# design.net
KiCad netlist of a schematic drawn in Altium Designer
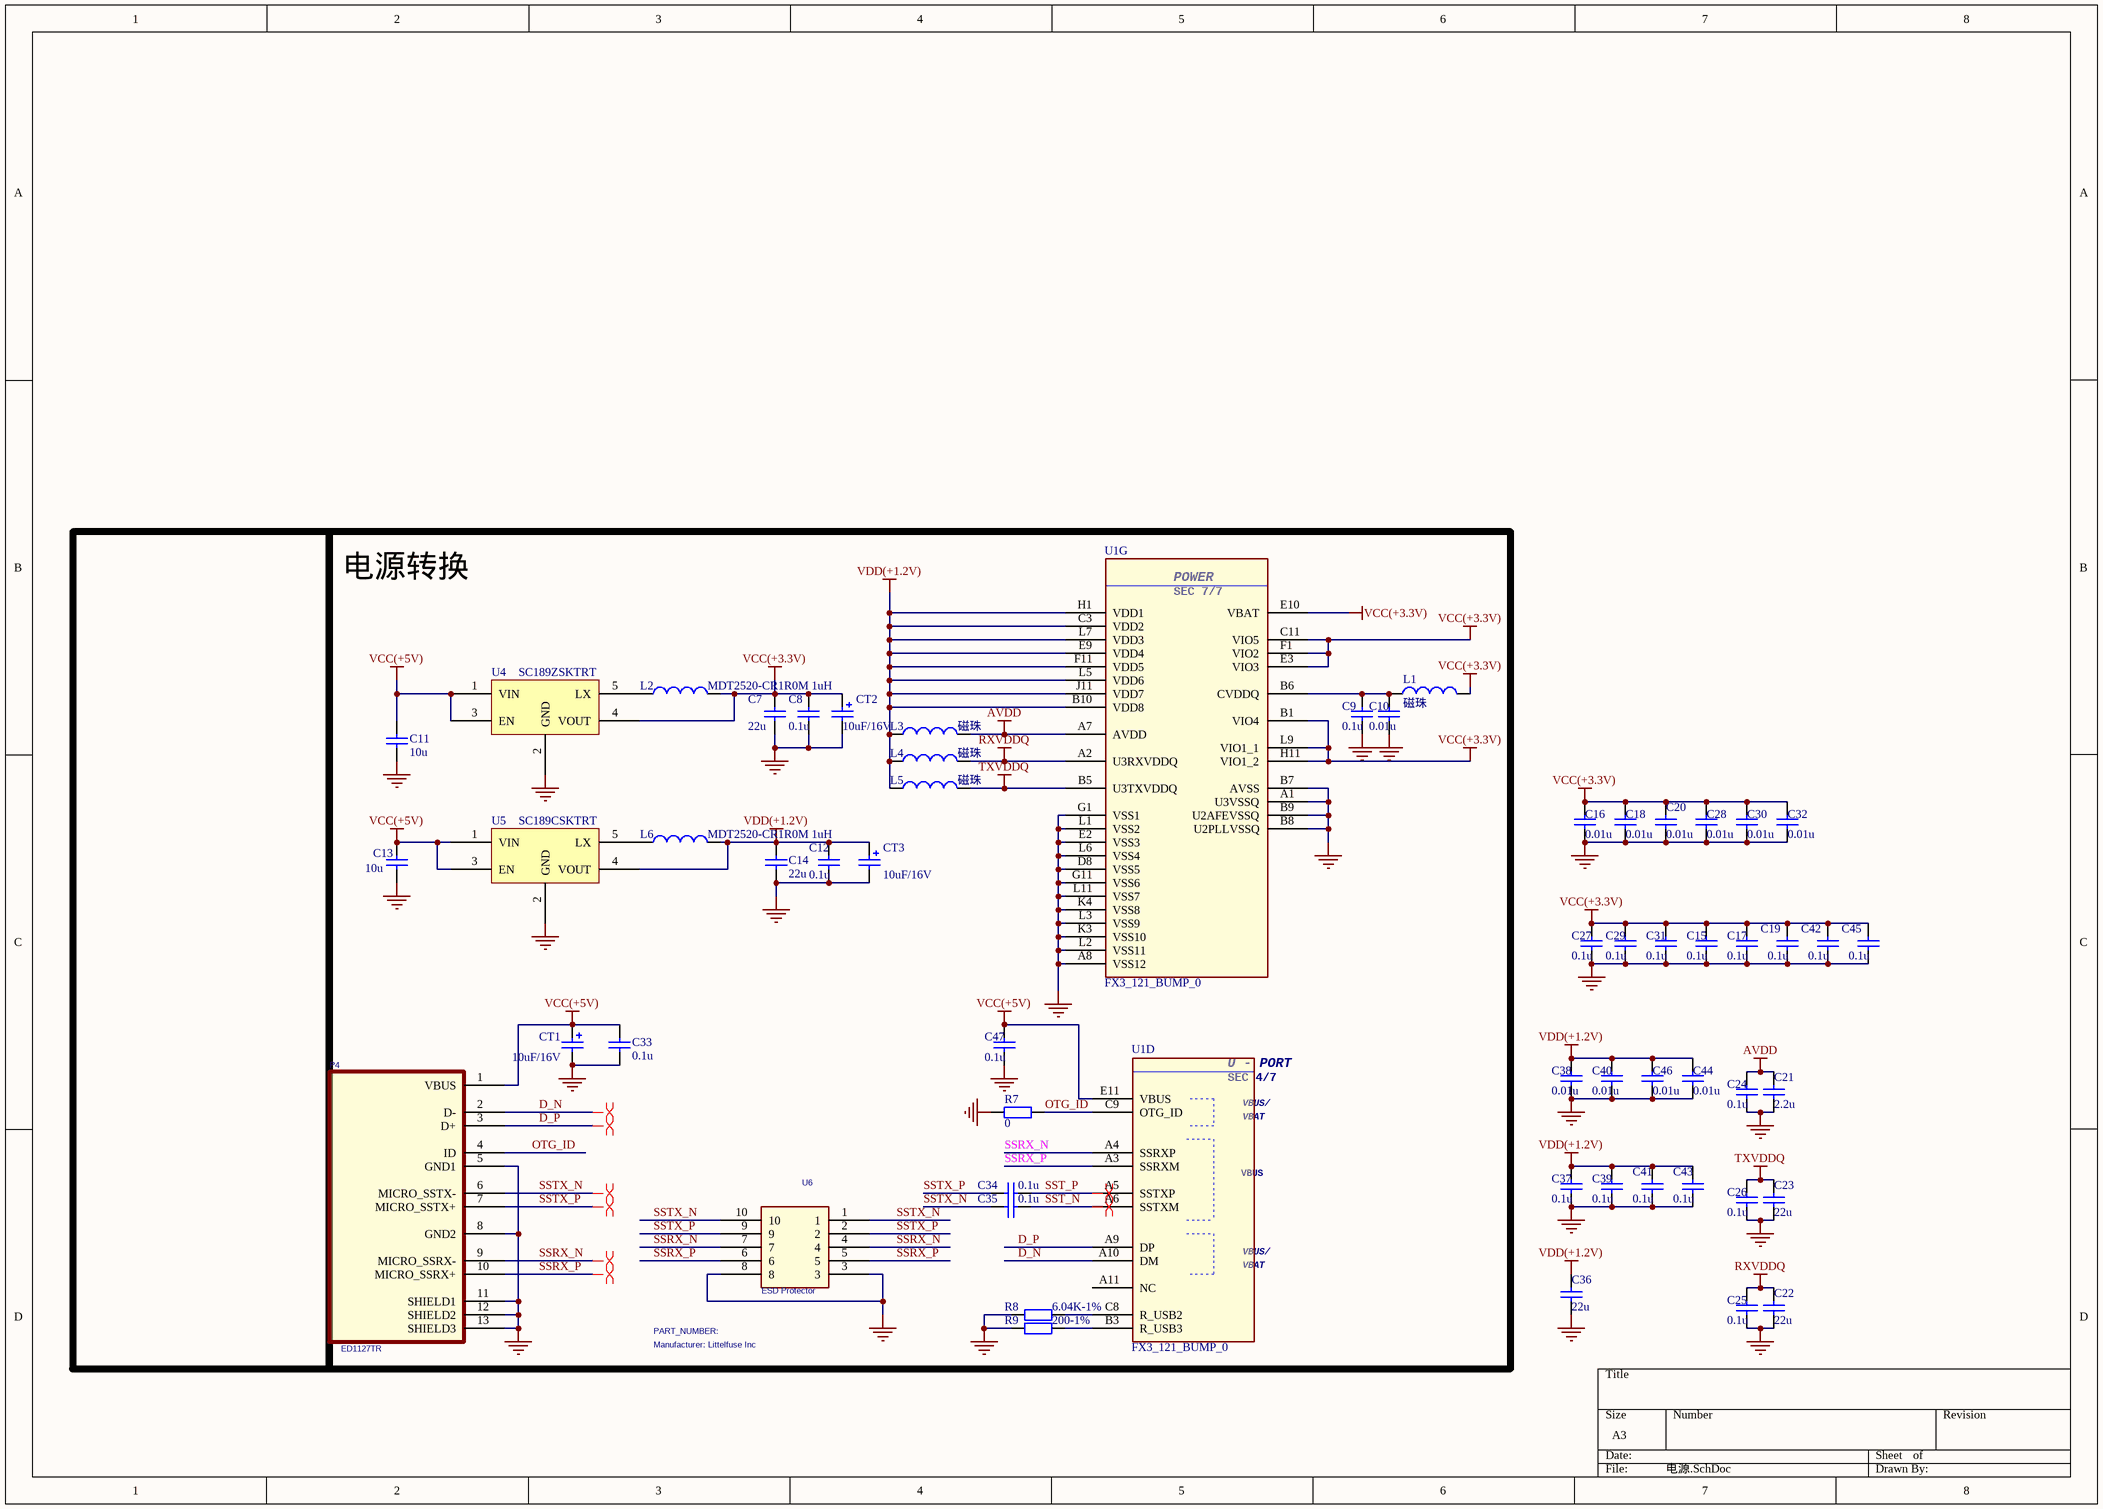
[diagram p0: 电源.SchDoc]

(export (version "E")
  (design (tool "Eeschema 10.0.6"))
  (components
    (comp (ref "C7")
      (value "22u")
      (footprint "C0805S-CAP")
      (description "Capacitor")
      (fields (field (name "PUBLISHER") "Altium Limited"))
      (libsource (lib "USB_CAMERA") (part "CAP0805"))
    )
    (comp (ref "C8")
      (value "0.1u")
      (footprint "0603S-CAP")
      (description "Capacitor")
      (fields (field (name "PUBLISHER") "Altium Limited"))
      (libsource (lib "USB_CAMERA") (part "CAP0805"))
    )
    (comp (ref "C9")
      (value "0.1u")
      (footprint "C0402")
      (description "Capacitor")
      (fields (field (name "PUBLISHER") "Altium Limited"))
      (libsource (lib "WM360") (part "CAP0805"))
    )
    (comp (ref "C10")
      (value "0.01u")
      (footprint "C0402")
      (description "Capacitor")
      (fields (field (name "PUBLISHER") "Altium Limited"))
      (libsource (lib "WM360") (part "CAP0805"))
    )
    (comp (ref "C11")
      (value "10u")
      (footprint "C0805S-CAP")
      (description "Capacitor")
      (fields (field (name "PUBLISHER") "Altium Limited"))
      (libsource (lib "USB_CAMERA") (part "CAP0805"))
    )
    (comp (ref "C12")
      (value "0.1u")
      (footprint "0603S-CAP")
      (description "Capacitor")
      (fields (field (name "PUBLISHER") "Altium Limited"))
      (libsource (lib "USB_CAMERA") (part "CAP0805"))
    )
    (comp (ref "C13")
      (value "10u")
      (footprint "C0805S-CAP")
      (description "Capacitor")
      (fields (field (name "PUBLISHER") "Altium Limited"))
      (libsource (lib "Miscellaneous Devices") (part "Cap"))
    )
    (comp (ref "C14")
      (value "22u")
      (footprint "C0805S-CAP")
      (description "Capacitor")
      (fields (field (name "PUBLISHER") "Altium Limited"))
      (libsource (lib "USB_CAMERA") (part "CAP0805"))
    )
    (comp (ref "C15")
      (value "0.1u")
      (footprint "C0402")
      (description "Capacitor")
      (fields (field (name "PUBLISHER") "Altium Limited"))
      (libsource (lib "WM360") (part "CAP0805"))
    )
    (comp (ref "C16")
      (value "0.01u")
      (footprint "C0402")
      (description "Capacitor")
      (fields (field (name "PUBLISHER") "Altium Limited"))
      (libsource (lib "WM360") (part "CAP0805"))
    )
    (comp (ref "C17")
      (value "0.1u")
      (footprint "C0402")
      (description "Capacitor")
      (fields (field (name "PUBLISHER") "Altium Limited"))
      (libsource (lib "WM360") (part "CAP0805"))
    )
    (comp (ref "C18")
      (value "0.01u")
      (footprint "C0402")
      (description "Capacitor")
      (fields (field (name "PUBLISHER") "Altium Limited"))
      (libsource (lib "WM360") (part "CAP0805"))
    )
    (comp (ref "C19")
      (value "0.1u")
      (footprint "C0402")
      (description "Capacitor")
      (fields (field (name "PUBLISHER") "Altium Limited"))
      (libsource (lib "WM360") (part "CAP0805"))
    )
    (comp (ref "C20")
      (value "0.01u")
      (footprint "C0402")
      (description "Capacitor")
      (fields (field (name "PUBLISHER") "Altium Limited"))
      (libsource (lib "WM360") (part "CAP0805"))
    )
    (comp (ref "C21")
      (value "2.2u")
      (footprint "C0805S-CAP")
      (description "Capacitor")
      (fields (field (name "PUBLISHER") "Altium Limited"))
      (libsource (lib "USB_CAMERA") (part "CAP0805"))
    )
    (comp (ref "C22")
      (value "22u")
      (footprint "C0805S-CAP")
      (description "Capacitor")
      (fields (field (name "PUBLISHER") "Altium Limited"))
      (libsource (lib "USB_CAMERA") (part "CAP0805"))
    )
    (comp (ref "C23")
      (value "22u")
      (footprint "C0805S-CAP")
      (description "Capacitor")
      (fields (field (name "PUBLISHER") "Altium Limited"))
      (libsource (lib "USB_CAMERA") (part "CAP0805"))
    )
    (comp (ref "C24")
      (value "0.1u")
      (footprint "C0402")
      (description "Capacitor")
      (fields (field (name "PUBLISHER") "Altium Limited"))
      (libsource (lib "WM360") (part "CAP0805"))
    )
    (comp (ref "C25")
      (value "0.1u")
      (footprint "C0402")
      (description "Capacitor")
      (fields (field (name "PUBLISHER") "Altium Limited"))
      (libsource (lib "WM360") (part "CAP0805"))
    )
    (comp (ref "C26")
      (value "0.1u")
      (footprint "C0402")
      (description "Capacitor")
      (fields (field (name "PUBLISHER") "Altium Limited"))
      (libsource (lib "WM360") (part "CAP0805"))
    )
    (comp (ref "C27")
      (value "0.1u")
      (footprint "C0402")
      (description "Capacitor")
      (fields (field (name "PUBLISHER") "Altium Limited"))
      (libsource (lib "WM360") (part "CAP0805"))
    )
    (comp (ref "C28")
      (value "0.01u")
      (footprint "C0402")
      (description "Capacitor")
      (fields (field (name "PUBLISHER") "Altium Limited"))
      (libsource (lib "WM360") (part "CAP0805"))
    )
    (comp (ref "C29")
      (value "0.1u")
      (footprint "C0402")
      (description "Capacitor")
      (fields (field (name "PUBLISHER") "Altium Limited"))
      (libsource (lib "WM360") (part "CAP0805"))
    )
    (comp (ref "C30")
      (value "0.01u")
      (footprint "C0402")
      (description "Capacitor")
      (fields (field (name "PUBLISHER") "Altium Limited"))
      (libsource (lib "WM360") (part "CAP0805"))
    )
    (comp (ref "C31")
      (value "0.1u")
      (footprint "C0402")
      (description "Capacitor")
      (fields (field (name "PUBLISHER") "Altium Limited"))
      (libsource (lib "WM360") (part "CAP0805"))
    )
    (comp (ref "C32")
      (value "0.01u")
      (footprint "C0402")
      (description "Capacitor")
      (fields (field (name "PUBLISHER") "Altium Limited"))
      (libsource (lib "WM360") (part "CAP0805"))
    )
    (comp (ref "C33")
      (value "0.1u")
      (footprint "0603S-CAP")
      (description "Capacitor")
      (fields (field (name "PUBLISHER") "Altium Limited"))
      (libsource (lib "USB_CAMERA") (part "CAP0805"))
    )
    (comp (ref "C34")
      (value "0.1u")
      (footprint "C0402")
      (description "Capacitor")
      (fields (field (name "PUBLISHER") "Altium Limited"))
      (libsource (lib "WM360") (part "CAP0805"))
    )
    (comp (ref "C35")
      (value "0.1u")
      (footprint "C0402")
      (description "Capacitor")
      (fields (field (name "PUBLISHER") "Altium Limited"))
      (libsource (lib "WM360") (part "CAP0805"))
    )
    (comp (ref "C36")
      (value "22u")
      (footprint "C0805S-CAP")
      (description "Capacitor")
      (fields (field (name "PUBLISHER") "Altium Limited"))
      (libsource (lib "USB_CAMERA") (part "CAP0805"))
    )
    (comp (ref "C37")
      (value "0.1u")
      (footprint "C0402")
      (description "Capacitor")
      (fields (field (name "PUBLISHER") "Altium Limited"))
      (libsource (lib "WM360") (part "CAP0805"))
    )
    (comp (ref "C38")
      (value "0.01u")
      (footprint "C0402")
      (description "Capacitor")
      (fields (field (name "PUBLISHER") "Altium Limited"))
      (libsource (lib "WM360") (part "CAP0805"))
    )
    (comp (ref "C39")
      (value "0.1u")
      (footprint "C0402")
      (description "Capacitor")
      (fields (field (name "PUBLISHER") "Altium Limited"))
      (libsource (lib "WM360") (part "CAP0805"))
    )
    (comp (ref "C40")
      (value "0.01u")
      (footprint "C0402")
      (description "Capacitor")
      (fields (field (name "PUBLISHER") "Altium Limited"))
      (libsource (lib "WM360") (part "CAP0805"))
    )
    (comp (ref "C41")
      (value "0.1u")
      (footprint "C0402")
      (description "Capacitor")
      (fields (field (name "PUBLISHER") "Altium Limited"))
      (libsource (lib "WM360") (part "CAP0805"))
    )
    (comp (ref "C42")
      (value "0.1u")
      (footprint "C0402")
      (description "Capacitor")
      (fields (field (name "PUBLISHER") "Altium Limited"))
      (libsource (lib "WM360") (part "CAP0805"))
    )
    (comp (ref "C43")
      (value "0.1u")
      (footprint "C0402")
      (description "Capacitor")
      (fields (field (name "PUBLISHER") "Altium Limited"))
      (libsource (lib "WM360") (part "CAP0805"))
    )
    (comp (ref "C44")
      (value "0.01u")
      (footprint "C0402")
      (description "Capacitor")
      (fields (field (name "PUBLISHER") "Altium Limited"))
      (libsource (lib "WM360") (part "CAP0805"))
    )
    (comp (ref "C45")
      (value "0.1u")
      (footprint "C0402")
      (description "Capacitor")
      (fields (field (name "PUBLISHER") "Altium Limited"))
      (libsource (lib "WM360") (part "CAP0805"))
    )
    (comp (ref "C46")
      (value "0.01u")
      (footprint "C0402")
      (description "Capacitor")
      (fields (field (name "PUBLISHER") "Altium Limited"))
      (libsource (lib "WM360") (part "CAP0805"))
    )
    (comp (ref "C47")
      (value "0.1u")
      (footprint "C0402")
      (description "Capacitor")
      (fields (field (name "PUBLISHER") "Altium Limited"))
      (libsource (lib "WM360") (part "CAP0805"))
    )
    (comp (ref "CT1")
      (value "10uF/16V")
      (footprint "钽电容（A型）")
      (description "Polarized Capacitor (Axial)")
      (fields (field (name "PUBLISHER") "Altium Limited"))
      (libsource (lib "Miscellaneous Devices") (part "Cap Pol2"))
    )
    (comp (ref "CT2")
      (value "10uF/16V")
      (footprint "钽电容（A型）")
      (description "Polarized Capacitor (Axial)")
      (fields (field (name "PUBLISHER") "Altium Limited"))
      (libsource (lib "Miscellaneous Devices") (part "Cap Pol2"))
    )
    (comp (ref "CT3")
      (value "10uF/16V")
      (footprint "钽电容（A型）")
      (description "Polarized Capacitor (Axial)")
      (fields (field (name "PUBLISHER") "Altium Limited"))
      (libsource (lib "Miscellaneous Devices") (part "Cap Pol2"))
    )
    (comp (ref "L1")
      (value "磁珠")
      (footprint "L0603")
      (description "Inductor")
      (fields (field (name "PUBLISHER") "Altium Limited"))
      (libsource (lib "Miscellaneous Devices") (part "Inductor"))
    )
    (comp (ref "L2")
      (value "MDT2520-CR1R0M 1uH")
      (footprint "L2520")
      (description "Inductor")
      (fields (field (name "PUBLISHER") "Altium Limited"))
      (libsource (lib "Miscellaneous Devices") (part "Inductor"))
    )
    (comp (ref "L3")
      (value "磁珠")
      (footprint "L0603")
      (description "Inductor")
      (fields (field (name "PUBLISHER") "Altium Limited"))
      (libsource (lib "Miscellaneous Devices") (part "Inductor"))
    )
    (comp (ref "L4")
      (value "磁珠")
      (footprint "L0603")
      (description "Inductor")
      (fields (field (name "PUBLISHER") "Altium Limited"))
      (libsource (lib "Miscellaneous Devices") (part "Inductor"))
    )
    (comp (ref "L5")
      (value "磁珠")
      (footprint "L0603")
      (description "Inductor")
      (fields (field (name "PUBLISHER") "Altium Limited"))
      (libsource (lib "Miscellaneous Devices") (part "Inductor"))
    )
    (comp (ref "L6")
      (value "MDT2520-CR1R0M 1uH")
      (footprint "L2520")
      (description "Inductor")
      (fields (field (name "PUBLISHER") "Altium Limited"))
      (libsource (lib "Miscellaneous Devices") (part "Inductor"))
    )
    (comp (ref "P4")
      (value "ED1127TR")
      (footprint "ED1127TR")
      (description "CONN RCPT USB 3.0 MICRO-B SMD")
      (libsource (lib "USB_CAMERA") (part "GSB343133HR_2"))
    )
    (comp (ref "R7")
      (value "0")
      (footprint "0603S-RES")
      (description "Resistor")
      (fields (field (name "PUBLISHER") "Altium Limited"))
      (libsource (lib "DM642") (part "Res2"))
    )
    (comp (ref "R8")
      (value "6.04K-1%")
      (footprint "0603S-RES")
      (description "Resistor")
      (fields (field (name "PUBLISHER") "Altium Limited"))
      (libsource (lib "DM642") (part "Res2"))
    )
    (comp (ref "R9")
      (value "200-1%")
      (footprint "0603S-RES")
      (description "Resistor")
      (fields (field (name "PUBLISHER") "Altium Limited"))
      (libsource (lib "DM642") (part "Res2"))
    )
    (comp (ref "U1")
      (value "FX3_121_BUMP_0")
      (footprint "121_BGA_FX3")
      (libsource (lib "USB_CAMERA") (part "FX3_121_BUMP_0"))
    )
    (comp (ref "U4")
      (value "SC189ZSKTRT")
      (footprint "SOT23-5")
      (libsource (lib "MT9D112") (part "PAM3101DAB150"))
    )
    (comp (ref "U5")
      (value "SC189CSKTRT")
      (footprint "SOT23-5")
      (libsource (lib "MT9D112") (part "PAM3101DAB150"))
    )
    (comp (ref "U6")
      (value "ESD Protector")
      (footprint "UDFN10_SP3010")
      (description "TVS DIODE 6VWM 12.3VC UDFN")
      (fields (field (name "MANUFACTURER") "Littelfuse Inc") (field (name "PART NUMBER") "SP3010-04UTG"))
      (libsource (lib "*") (part "AZ1065-06Q_0"))
    )
  )
  (nets
    (net (code "1") (name "/D_N") (class "Default")
      (node (ref "P4") (pin "2") (pinfunction "D-_2") (pintype "passive"))
      (node (ref "U1") (pin "A10") (pinfunction "DM_A10") (pintype "passive"))
    )
    (net (code "2") (name "/D_P") (class "Default")
      (node (ref "P4") (pin "3") (pinfunction "D+_3") (pintype "passive"))
      (node (ref "U1") (pin "A9") (pinfunction "DP_A9") (pintype "passive"))
    )
    (net (code "3") (name "/OTG_ID") (class "Default")
      (node (ref "P4") (pin "4") (pinfunction "ID_4") (pintype "passive"))
      (node (ref "R7") (pin "1") (pinfunction "1_1") (pintype "passive"))
      (node (ref "U1") (pin "C9") (pinfunction "OTG_ID_C9") (pintype "passive"))
    )
    (net (code "4") (name "/SSRX_N") (class "Default")
      (node (ref "P4") (pin "9") (pinfunction "MICRO_SSRX-_9") (pintype "passive"))
      (node (ref "U1") (pin "A4") (pinfunction "SSRXP_A4") (pintype "passive"))
      (node (ref "U6") (pin "4") (pinfunction "4_4") (pintype "passive"))
      (node (ref "U6") (pin "7") (pinfunction "7_7") (pintype "passive"))
    )
    (net (code "5") (name "/SSRX_P") (class "Default")
      (node (ref "P4") (pin "10") (pinfunction "MICRO_SSRX+_10") (pintype "passive"))
      (node (ref "U1") (pin "A3") (pinfunction "SSRXM_A3") (pintype "passive"))
      (node (ref "U6") (pin "5") (pinfunction "5_5") (pintype "passive"))
      (node (ref "U6") (pin "6") (pinfunction "6_6") (pintype "passive"))
    )
    (net (code "6") (name "/SSTX_N") (class "Default")
      (node (ref "C35") (pin "1") (pinfunction "1_1") (pintype "passive"))
      (node (ref "P4") (pin "6") (pinfunction "MICRO_SSTX-_6") (pintype "passive"))
      (node (ref "U6") (pin "1") (pinfunction "1_1") (pintype "passive"))
      (node (ref "U6") (pin "10") (pinfunction "10_10") (pintype "passive"))
    )
    (net (code "7") (name "/SSTX_P") (class "Default")
      (node (ref "C34") (pin "1") (pinfunction "1_1") (pintype "passive"))
      (node (ref "P4") (pin "7") (pinfunction "MICRO_SSTX+_7") (pintype "passive"))
      (node (ref "U6") (pin "2") (pinfunction "2_2") (pintype "passive"))
      (node (ref "U6") (pin "9") (pinfunction "9_9") (pintype "passive"))
    )
    (net (code "8") (name "/SST_N") (class "Default")
      (node (ref "C35") (pin "2") (pinfunction "2_2") (pintype "passive"))
      (node (ref "U1") (pin "A6") (pinfunction "SSTXM_A6") (pintype "passive"))
    )
    (net (code "9") (name "/SST_P") (class "Default")
      (node (ref "C34") (pin "2") (pinfunction "2_2") (pintype "passive"))
      (node (ref "U1") (pin "A5") (pinfunction "SSTXP_A5") (pintype "passive"))
    )
    (net (code "10") (name "AVDD") (class "Default")
      (node (ref "C21") (pin "2") (pinfunction "2_2") (pintype "passive"))
      (node (ref "C24") (pin "1") (pinfunction "1_1") (pintype "passive"))
      (node (ref "L3") (pin "2") (pinfunction "2_2") (pintype "passive"))
      (node (ref "U1") (pin "A7") (pinfunction "AVDD_A7") (pintype "passive"))
    )
    (net (code "11") (name "GND") (class "Default")
      (node (ref "C10") (pin "2") (pinfunction "2_2") (pintype "passive"))
      (node (ref "C11") (pin "1") (pinfunction "1_1") (pintype "passive"))
      (node (ref "C12") (pin "2") (pinfunction "2_2") (pintype "passive"))
      (node (ref "C13") (pin "1") (pinfunction "1_1") (pintype "passive"))
      (node (ref "C14") (pin "1") (pinfunction "1_1") (pintype "passive"))
      (node (ref "C15") (pin "2") (pinfunction "2_2") (pintype "passive"))
      (node (ref "C16") (pin "2") (pinfunction "2_2") (pintype "passive"))
      (node (ref "C17") (pin "2") (pinfunction "2_2") (pintype "passive"))
      (node (ref "C18") (pin "2") (pinfunction "2_2") (pintype "passive"))
      (node (ref "C19") (pin "2") (pinfunction "2_2") (pintype "passive"))
      (node (ref "C20") (pin "2") (pinfunction "2_2") (pintype "passive"))
      (node (ref "C21") (pin "1") (pinfunction "1_1") (pintype "passive"))
      (node (ref "C22") (pin "1") (pinfunction "1_1") (pintype "passive"))
      (node (ref "C23") (pin "1") (pinfunction "1_1") (pintype "passive"))
      (node (ref "C24") (pin "2") (pinfunction "2_2") (pintype "passive"))
      (node (ref "C25") (pin "2") (pinfunction "2_2") (pintype "passive"))
      (node (ref "C26") (pin "2") (pinfunction "2_2") (pintype "passive"))
      (node (ref "C27") (pin "2") (pinfunction "2_2") (pintype "passive"))
      (node (ref "C28") (pin "2") (pinfunction "2_2") (pintype "passive"))
      (node (ref "C29") (pin "2") (pinfunction "2_2") (pintype "passive"))
      (node (ref "C30") (pin "2") (pinfunction "2_2") (pintype "passive"))
      (node (ref "C31") (pin "2") (pinfunction "2_2") (pintype "passive"))
      (node (ref "C32") (pin "2") (pinfunction "2_2") (pintype "passive"))
      (node (ref "C33") (pin "2") (pinfunction "2_2") (pintype "passive"))
      (node (ref "C36") (pin "1") (pinfunction "1_1") (pintype "passive"))
      (node (ref "C37") (pin "2") (pinfunction "2_2") (pintype "passive"))
      (node (ref "C38") (pin "2") (pinfunction "2_2") (pintype "passive"))
      (node (ref "C39") (pin "2") (pinfunction "2_2") (pintype "passive"))
      (node (ref "C40") (pin "2") (pinfunction "2_2") (pintype "passive"))
      (node (ref "C41") (pin "2") (pinfunction "2_2") (pintype "passive"))
      (node (ref "C42") (pin "2") (pinfunction "2_2") (pintype "passive"))
      (node (ref "C43") (pin "2") (pinfunction "2_2") (pintype "passive"))
      (node (ref "C44") (pin "2") (pinfunction "2_2") (pintype "passive"))
      (node (ref "C45") (pin "2") (pinfunction "2_2") (pintype "passive"))
      (node (ref "C46") (pin "2") (pinfunction "2_2") (pintype "passive"))
      (node (ref "C47") (pin "2") (pinfunction "2_2") (pintype "passive"))
      (node (ref "C7") (pin "1") (pinfunction "1_1") (pintype "passive"))
      (node (ref "C8") (pin "2") (pinfunction "2_2") (pintype "passive"))
      (node (ref "C9") (pin "2") (pinfunction "2_2") (pintype "passive"))
      (node (ref "CT1") (pin "2") (pinfunction "2_2") (pintype "passive"))
      (node (ref "CT2") (pin "2") (pinfunction "2_2") (pintype "passive"))
      (node (ref "CT3") (pin "2") (pinfunction "2_2") (pintype "passive"))
      (node (ref "P4") (pin "11") (pinfunction "SHIELD1_11") (pintype "passive"))
      (node (ref "P4") (pin "12") (pinfunction "SHIELD2_12") (pintype "passive"))
      (node (ref "P4") (pin "13") (pinfunction "SHIELD3_13") (pintype "passive"))
      (node (ref "P4") (pin "5") (pinfunction "GND1_5") (pintype "passive"))
      (node (ref "P4") (pin "8") (pinfunction "GND2_8") (pintype "passive"))
      (node (ref "R7") (pin "2") (pinfunction "2_2") (pintype "passive"))
      (node (ref "R8") (pin "2") (pinfunction "2_2") (pintype "passive"))
      (node (ref "R9") (pin "2") (pinfunction "2_2") (pintype "passive"))
      (node (ref "U1") (pin "A1") (pinfunction "U3VSSQ_A1") (pintype "passive"))
      (node (ref "U1") (pin "A8") (pinfunction "VSS12_A8") (pintype "passive"))
      (node (ref "U1") (pin "B7") (pinfunction "AVSS_B7") (pintype "passive"))
      (node (ref "U1") (pin "B8") (pinfunction "U2PLLVSSQ_B8") (pintype "passive"))
      (node (ref "U1") (pin "B9") (pinfunction "U2AFEVSSQ_B9") (pintype "passive"))
      (node (ref "U1") (pin "D8") (pinfunction "VSS5_D8") (pintype "passive"))
      (node (ref "U1") (pin "E2") (pinfunction "VSS3_E2") (pintype "passive"))
      (node (ref "U1") (pin "G1") (pinfunction "VSS1_G1") (pintype "passive"))
      (node (ref "U1") (pin "G11") (pinfunction "VSS6_G11") (pintype "passive"))
      (node (ref "U1") (pin "K3") (pinfunction "VSS10_K3") (pintype "passive"))
      (node (ref "U1") (pin "K4") (pinfunction "VSS8_K4") (pintype "passive"))
      (node (ref "U1") (pin "L1") (pinfunction "VSS2_L1") (pintype "passive"))
      (node (ref "U1") (pin "L11") (pinfunction "VSS7_L11") (pintype "passive"))
      (node (ref "U1") (pin "L2") (pinfunction "VSS11_L2") (pintype "passive"))
      (node (ref "U1") (pin "L3") (pinfunction "VSS9_L3") (pintype "passive"))
      (node (ref "U1") (pin "L6") (pinfunction "VSS4_L6") (pintype "passive"))
      (node (ref "U4") (pin "2") (pinfunction "GND_2") (pintype "passive"))
      (node (ref "U5") (pin "2") (pinfunction "GND_2") (pintype "passive"))
      (node (ref "U6") (pin "3") (pinfunction "3_3") (pintype "passive"))
      (node (ref "U6") (pin "8") (pinfunction "8_8") (pintype "passive"))
    )
    (net (code "12") (name "Net-(U1D-R_USB2)") (class "Default")
      (node (ref "R8") (pin "1") (pinfunction "1_1") (pintype "passive"))
      (node (ref "U1") (pin "C8") (pinfunction "R_USB2_C8") (pintype "passive"))
    )
    (net (code "13") (name "Net-(U1D-R_USB3)") (class "Default")
      (node (ref "R9") (pin "1") (pinfunction "1_1") (pintype "passive"))
      (node (ref "U1") (pin "B3") (pinfunction "R_USB3_B3") (pintype "passive"))
    )
    (net (code "14") (name "Net-(U1G-CVDDQ)") (class "Default")
      (node (ref "C10") (pin "1") (pinfunction "1_1") (pintype "passive"))
      (node (ref "C9") (pin "1") (pinfunction "1_1") (pintype "passive"))
      (node (ref "L1") (pin "1") (pinfunction "1_1") (pintype "passive"))
      (node (ref "U1") (pin "B6") (pinfunction "CVDDQ_B6") (pintype "passive"))
    )
    (net (code "15") (name "Net-(U4-LX)") (class "Default")
      (node (ref "L2") (pin "1") (pinfunction "1_1") (pintype "passive"))
      (node (ref "U4") (pin "5") (pinfunction "LX_5") (pintype "passive"))
    )
    (net (code "16") (name "Net-(U5-LX)") (class "Default")
      (node (ref "L6") (pin "1") (pinfunction "1_1") (pintype "passive"))
      (node (ref "U5") (pin "5") (pinfunction "LX_5") (pintype "passive"))
    )
    (net (code "17") (name "RXVDDQ") (class "Default")
      (node (ref "C22") (pin "2") (pinfunction "2_2") (pintype "passive"))
      (node (ref "C25") (pin "1") (pinfunction "1_1") (pintype "passive"))
      (node (ref "L4") (pin "2") (pinfunction "2_2") (pintype "passive"))
      (node (ref "U1") (pin "A2") (pinfunction "U3RXVDDQ_A2") (pintype "passive"))
    )
    (net (code "18") (name "TXVDDQ") (class "Default")
      (node (ref "C23") (pin "2") (pinfunction "2_2") (pintype "passive"))
      (node (ref "C26") (pin "1") (pinfunction "1_1") (pintype "passive"))
      (node (ref "L5") (pin "2") (pinfunction "2_2") (pintype "passive"))
      (node (ref "U1") (pin "B5") (pinfunction "U3TXVDDQ_B5") (pintype "passive"))
    )
    (net (code "19") (name "VCC(+3.3V)") (class "Default")
      (node (ref "C15") (pin "1") (pinfunction "1_1") (pintype "passive"))
      (node (ref "C16") (pin "1") (pinfunction "1_1") (pintype "passive"))
      (node (ref "C17") (pin "1") (pinfunction "1_1") (pintype "passive"))
      (node (ref "C18") (pin "1") (pinfunction "1_1") (pintype "passive"))
      (node (ref "C19") (pin "1") (pinfunction "1_1") (pintype "passive"))
      (node (ref "C20") (pin "1") (pinfunction "1_1") (pintype "passive"))
      (node (ref "C27") (pin "1") (pinfunction "1_1") (pintype "passive"))
      (node (ref "C28") (pin "1") (pinfunction "1_1") (pintype "passive"))
      (node (ref "C29") (pin "1") (pinfunction "1_1") (pintype "passive"))
      (node (ref "C30") (pin "1") (pinfunction "1_1") (pintype "passive"))
      (node (ref "C31") (pin "1") (pinfunction "1_1") (pintype "passive"))
      (node (ref "C32") (pin "1") (pinfunction "1_1") (pintype "passive"))
      (node (ref "C42") (pin "1") (pinfunction "1_1") (pintype "passive"))
      (node (ref "C45") (pin "1") (pinfunction "1_1") (pintype "passive"))
      (node (ref "C7") (pin "2") (pinfunction "2_2") (pintype "passive"))
      (node (ref "C8") (pin "1") (pinfunction "1_1") (pintype "passive"))
      (node (ref "CT2") (pin "1") (pinfunction "1_1") (pintype "passive"))
      (node (ref "L1") (pin "2") (pinfunction "2_2") (pintype "passive"))
      (node (ref "L2") (pin "2") (pinfunction "2_2") (pintype "passive"))
      (node (ref "U1") (pin "B1") (pinfunction "VIO4_B1") (pintype "passive"))
      (node (ref "U1") (pin "C11") (pinfunction "VIO5_C11") (pintype "passive"))
      (node (ref "U1") (pin "E10") (pinfunction "VBAT_E10") (pintype "passive"))
      (node (ref "U1") (pin "E3") (pinfunction "VIO3_E3") (pintype "passive"))
      (node (ref "U1") (pin "F1") (pinfunction "VIO2_F1") (pintype "passive"))
      (node (ref "U1") (pin "H11") (pinfunction "VIO1_2_H11") (pintype "passive"))
      (node (ref "U1") (pin "L9") (pinfunction "VIO1_1_L9") (pintype "passive"))
      (node (ref "U4") (pin "4") (pinfunction "VOUT_4") (pintype "passive"))
    )
    (net (code "20") (name "VCC(+5V)") (class "Default")
      (node (ref "C11") (pin "2") (pinfunction "2_2") (pintype "passive"))
      (node (ref "C13") (pin "2") (pinfunction "2_2") (pintype "passive"))
      (node (ref "C33") (pin "1") (pinfunction "1_1") (pintype "passive"))
      (node (ref "C47") (pin "1") (pinfunction "1_1") (pintype "passive"))
      (node (ref "CT1") (pin "1") (pinfunction "1_1") (pintype "passive"))
      (node (ref "P4") (pin "1") (pinfunction "VBUS_1") (pintype "passive"))
      (node (ref "U1") (pin "E11") (pinfunction "VBUS_E11") (pintype "passive"))
      (node (ref "U4") (pin "1") (pinfunction "VIN_1") (pintype "passive"))
      (node (ref "U4") (pin "3") (pinfunction "EN_3") (pintype "passive"))
      (node (ref "U5") (pin "1") (pinfunction "VIN_1") (pintype "passive"))
      (node (ref "U5") (pin "3") (pinfunction "EN_3") (pintype "passive"))
    )
    (net (code "21") (name "VDD(+1.2V)") (class "Default")
      (node (ref "C12") (pin "1") (pinfunction "1_1") (pintype "passive"))
      (node (ref "C14") (pin "2") (pinfunction "2_2") (pintype "passive"))
      (node (ref "C36") (pin "2") (pinfunction "2_2") (pintype "passive"))
      (node (ref "C37") (pin "1") (pinfunction "1_1") (pintype "passive"))
      (node (ref "C38") (pin "1") (pinfunction "1_1") (pintype "passive"))
      (node (ref "C39") (pin "1") (pinfunction "1_1") (pintype "passive"))
      (node (ref "C40") (pin "1") (pinfunction "1_1") (pintype "passive"))
      (node (ref "C41") (pin "1") (pinfunction "1_1") (pintype "passive"))
      (node (ref "C43") (pin "1") (pinfunction "1_1") (pintype "passive"))
      (node (ref "C44") (pin "1") (pinfunction "1_1") (pintype "passive"))
      (node (ref "C46") (pin "1") (pinfunction "1_1") (pintype "passive"))
      (node (ref "CT3") (pin "1") (pinfunction "1_1") (pintype "passive"))
      (node (ref "L3") (pin "1") (pinfunction "1_1") (pintype "passive"))
      (node (ref "L4") (pin "1") (pinfunction "1_1") (pintype "passive"))
      (node (ref "L5") (pin "1") (pinfunction "1_1") (pintype "passive"))
      (node (ref "L6") (pin "2") (pinfunction "2_2") (pintype "passive"))
      (node (ref "U1") (pin "B10") (pinfunction "VDD8_B10") (pintype "passive"))
      (node (ref "U1") (pin "C3") (pinfunction "VDD2_C3") (pintype "passive"))
      (node (ref "U1") (pin "E9") (pinfunction "VDD4_E9") (pintype "passive"))
      (node (ref "U1") (pin "F11") (pinfunction "VDD5_F11") (pintype "passive"))
      (node (ref "U1") (pin "H1") (pinfunction "VDD1_H1") (pintype "passive"))
      (node (ref "U1") (pin "J11") (pinfunction "VDD7_J11") (pintype "passive"))
      (node (ref "U1") (pin "L5") (pinfunction "VDD6_L5") (pintype "passive"))
      (node (ref "U1") (pin "L7") (pinfunction "VDD3_L7") (pintype "passive"))
      (node (ref "U5") (pin "4") (pinfunction "VOUT_4") (pintype "passive"))
    )
    (net (code "22") (name "unconnected-(U1D-NC-PadA11)") (class "Default")
      (node (ref "U1") (pin "A11") (pinfunction "NC_A11") (pintype "passive"))
    )
  )
)
